# design.net
KiCad netlist of a schematic drawn in EasyEDA Pro
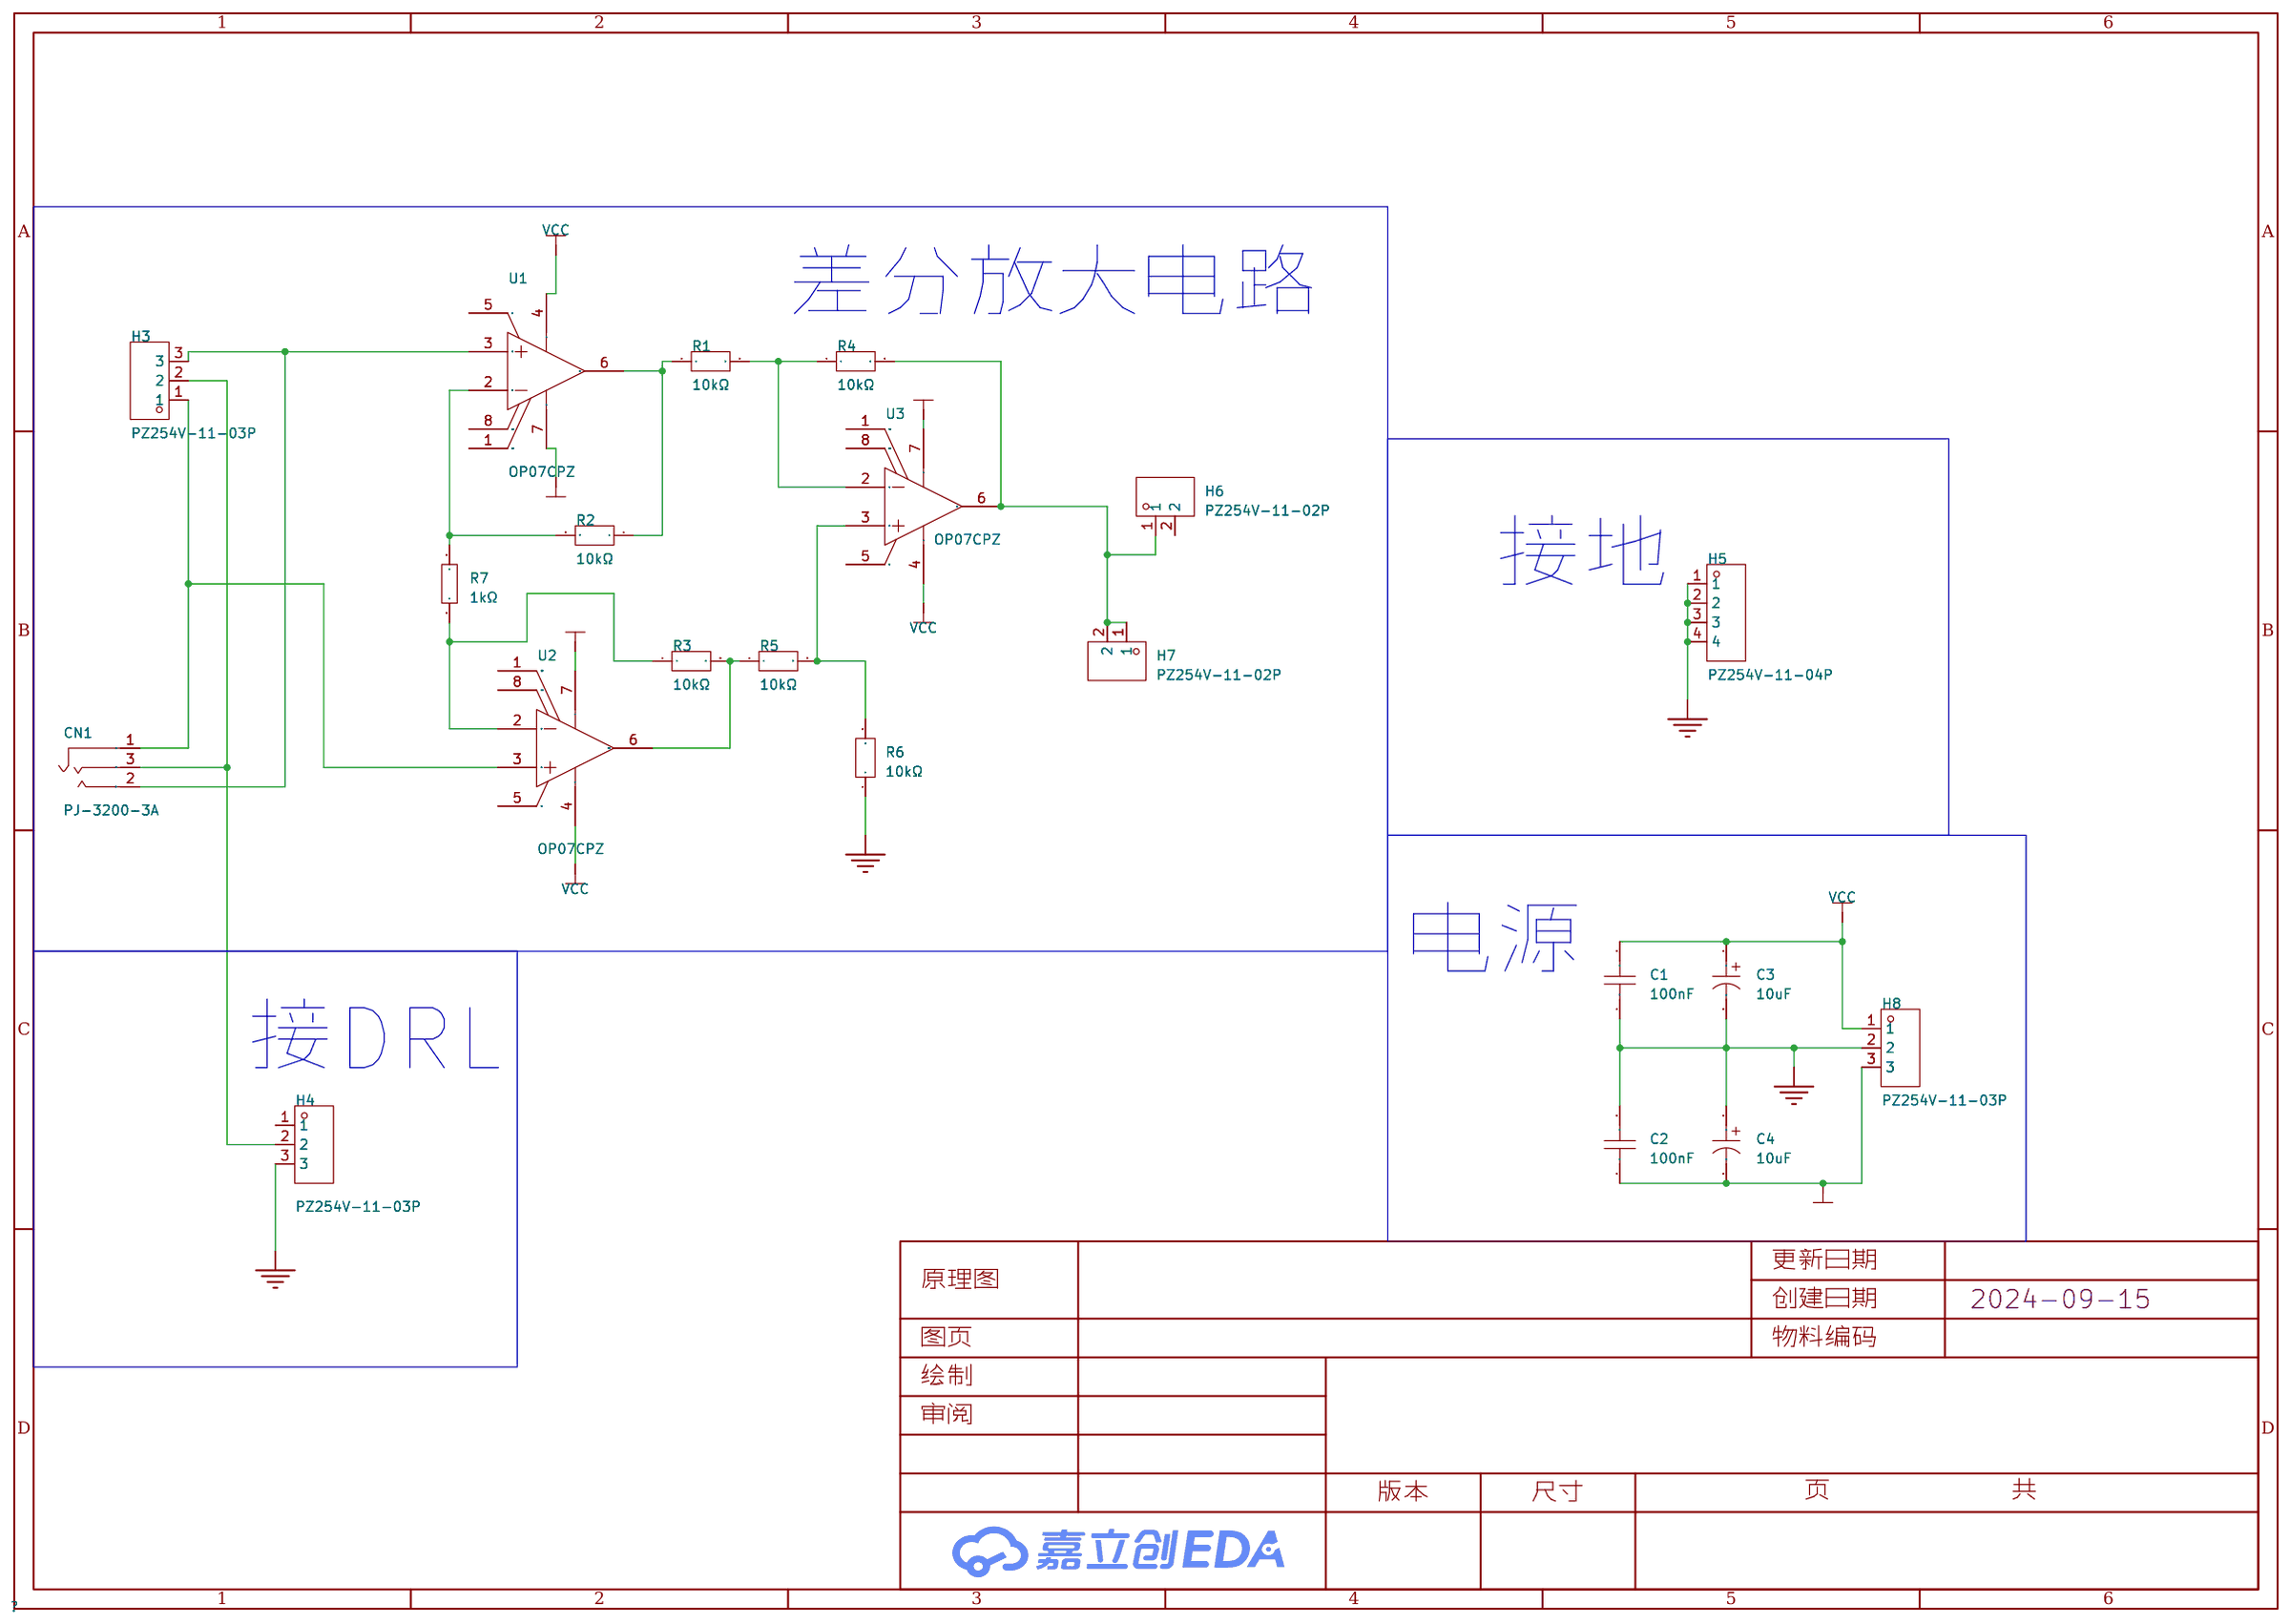
[diagram p0: schematic sheet]

(export (version "E")
  (design (tool "Eeschema 10.0.6"))
  (components
    (comp (ref "C1")
      (value "100nF")
      (footprint "easyedapro:CAP-TH_L13.0-W6.0-P10.0-D0.6")
      (description "容值:100nF;精度:±10%;电压(AC):275V;等级:X2;")
      (fields (field (name "Manufacturer Part") "1X2H410K275-11") (field (name "Manufacturer") "BM(丰明电容)"))
      (libsource (lib "easyedapro") (part "1X2H410K275-11"))
    )
    (comp (ref "C2")
      (value "100nF")
      (footprint "easyedapro:CAP-TH_L13.0-W6.0-P10.0-D0.6")
      (description "容值:100nF;精度:±10%;电压(AC):275V;等级:X2;")
      (fields (field (name "Manufacturer Part") "1X2H410K275-11") (field (name "Manufacturer") "BM(丰明电容)"))
      (libsource (lib "easyedapro") (part "1X2H410K275-11"))
    )
    (comp (ref "C3")
      (value "10uF")
      (footprint "easyedapro:CAP-TH_BD10.0-P5.00-D0.6-FD")
      (description "容值:10uF;精度:±20%;额定电压:250V;纹波电流:175mA@120Hz;等效串联电阻:-;")
      (fields
        (field (name "Manufacturer Part") "UCS2E100MPD1TD")
        (field (name "Manufacturer") "Nichicon(尼吉康)")
      )
      (libsource (lib "easyedapro") (part "UCS2E100MPD1TD"))
    )
    (comp (ref "C4")
      (value "10uF")
      (footprint "easyedapro:CAP-TH_BD10.0-P5.00-D0.6-FD")
      (description "容值:10uF;精度:±20%;额定电压:250V;纹波电流:175mA@120Hz;等效串联电阻:-;")
      (fields
        (field (name "Manufacturer Part") "UCS2E100MPD1TD")
        (field (name "Manufacturer") "Nichicon(尼吉康)")
      )
      (libsource (lib "easyedapro") (part "UCS2E100MPD1TD"))
    )
    (comp (ref "CN1")
      (value "PJ-3200-3A")
      (footprint "easyedapro:AUDIO-TH_PJ-3200-3A")
      (description "连接器类型:3.5mm耳机座;额定电流:500mA;额定电压:30V;工作温度范围:-20°C~+70°C;")
      (fields (field (name "Manufacturer") "韩国韩荣"))
      (libsource (lib "easyedapro") (part "PJ-3200-3A"))
    )
    (comp (ref "H3")
      (value "PZ254V-11-03P")
      (footprint "easyedapro:HDR-TH_3P-P2.54-V-M")
      (fields (field (name "Manufacturer") "XFCN(兴飞)"))
      (libsource (lib "easyedapro") (part "PZ254V-11-03P_C2937625"))
    )
    (comp (ref "H4")
      (value "PZ254V-11-03P")
      (footprint "easyedapro:HDR-TH_3P-P2.54-V-M")
      (fields (field (name "Manufacturer") "XFCN(兴飞)"))
      (libsource (lib "easyedapro") (part "PZ254V-11-03P_C2937625"))
    )
    (comp (ref "H5")
      (value "PZ254V-11-04P")
      (footprint "easyedapro:HDR-TH_4P-P2.54-V-M")
      (fields (field (name "Manufacturer") "XFCN(兴飞)"))
      (libsource (lib "easyedapro") (part "PZ254V-11-04P_C2691448"))
    )
    (comp (ref "H6")
      (value "PZ254V-11-02P")
      (footprint "easyedapro:HDR-TH_2P-P2.54-V-M")
      (fields (field (name "Manufacturer") "XFCN(兴飞)"))
      (libsource (lib "easyedapro") (part "PZ254V-11-02P"))
    )
    (comp (ref "H7")
      (value "PZ254V-11-02P")
      (footprint "easyedapro:HDR-TH_2P-P2.54-V-M")
      (fields (field (name "Manufacturer") "XFCN(兴飞)"))
      (libsource (lib "easyedapro") (part "PZ254V-11-02P"))
    )
    (comp (ref "H8")
      (value "PZ254V-11-03P")
      (footprint "easyedapro:HDR-TH_3P-P2.54-V-M")
      (fields (field (name "Manufacturer") "XFCN(兴飞)"))
      (libsource (lib "easyedapro") (part "PZ254V-11-03P_C2937625"))
    )
    (comp (ref "R1")
      (value "10kΩ")
      (footprint "easyedapro:RES-TH_BD2.4-L6.3-P10.30-D0.6")
      (description "电阻类型:金属膜电阻;阻值:10kΩ;精度:±1%;功率:250mW;温度系数:±50ppm/°C;")
      (fields
        (field (name "Manufacturer Part") "RN1/4W10KFT/BA1")
        (field (name "Manufacturer") "Tyohm(幸亚电阻)")
      )
      (libsource (lib "easyedapro") (part "RN 1/4W 10K F T/B A1"))
    )
    (comp (ref "R2")
      (value "10kΩ")
      (footprint "easyedapro:RES-TH_BD2.4-L6.3-P10.30-D0.6")
      (description "电阻类型:金属膜电阻;阻值:10kΩ;精度:±1%;功率:250mW;温度系数:±50ppm/°C;")
      (fields
        (field (name "Manufacturer Part") "RN1/4W10KFT/BA1")
        (field (name "Manufacturer") "Tyohm(幸亚电阻)")
      )
      (libsource (lib "easyedapro") (part "RN 1/4W 10K F T/B A1"))
    )
    (comp (ref "R3")
      (value "10kΩ")
      (footprint "easyedapro:RES-TH_BD2.4-L6.3-P10.30-D0.6")
      (description "电阻类型:金属膜电阻;阻值:10kΩ;精度:±1%;功率:250mW;温度系数:±50ppm/°C;")
      (fields
        (field (name "Manufacturer Part") "RN1/4W10KFT/BA1")
        (field (name "Manufacturer") "Tyohm(幸亚电阻)")
      )
      (libsource (lib "easyedapro") (part "RN 1/4W 10K F T/B A1"))
    )
    (comp (ref "R4")
      (value "10kΩ")
      (footprint "easyedapro:RES-TH_BD2.4-L6.3-P10.30-D0.6")
      (description "电阻类型:金属膜电阻;阻值:10kΩ;精度:±1%;功率:250mW;温度系数:±50ppm/°C;")
      (fields
        (field (name "Manufacturer Part") "RN1/4W10KFT/BA1")
        (field (name "Manufacturer") "Tyohm(幸亚电阻)")
      )
      (libsource (lib "easyedapro") (part "RN 1/4W 10K F T/B A1"))
    )
    (comp (ref "R5")
      (value "10kΩ")
      (footprint "easyedapro:RES-TH_BD2.4-L6.3-P10.30-D0.6")
      (description "电阻类型:金属膜电阻;阻值:10kΩ;精度:±1%;功率:250mW;温度系数:±50ppm/°C;")
      (fields
        (field (name "Manufacturer Part") "RN1/4W10KFT/BA1")
        (field (name "Manufacturer") "Tyohm(幸亚电阻)")
      )
      (libsource (lib "easyedapro") (part "RN 1/4W 10K F T/B A1"))
    )
    (comp (ref "R6")
      (value "10kΩ")
      (footprint "easyedapro:RES-TH_BD2.4-L6.3-P10.30-D0.6")
      (description "电阻类型:金属膜电阻;阻值:10kΩ;精度:±1%;功率:250mW;温度系数:±50ppm/°C;")
      (fields
        (field (name "Manufacturer Part") "RN1/4W10KFT/BA1")
        (field (name "Manufacturer") "Tyohm(幸亚电阻)")
      )
      (libsource (lib "easyedapro") (part "RN 1/4W 10K F T/B A1"))
    )
    (comp (ref "R7")
      (value "1kΩ")
      (footprint "easyedapro:RES-TH_BD2.5-L6.5-P10.50-D0.6")
      (description "电阻类型:金属膜电阻;阻值:1kΩ;精度:±1%;功率:250mW;温度系数:±50ppm/°C;")
      (fields
        (field (name "Manufacturer Part") "MFR0W4F1001A50")
        (field (name "Manufacturer") "UNI-ROYAL(厚声)")
      )
      (libsource (lib "easyedapro") (part "MFR0W4F1001A50"))
    )
    (comp (ref "U1")
      (value "OP07CPZ")
      (footprint "easyedapro:PDIP-8_L9.3-W6.4-P2.54-LS7.6-BL")
      (description "超低失调电压运算放大器")
      (fields (field (name "Manufacturer") "ADI(亚德诺)"))
      (libsource (lib "easyedapro") (part "OP07CPZ"))
    )
    (comp (ref "U2")
      (value "OP07CPZ")
      (footprint "easyedapro:PDIP-8_L9.3-W6.4-P2.54-LS7.6-BL")
      (description "超低失调电压运算放大器")
      (fields (field (name "Manufacturer") "ADI(亚德诺)"))
      (libsource (lib "easyedapro") (part "OP07CPZ"))
    )
    (comp (ref "U3")
      (value "OP07CPZ")
      (footprint "easyedapro:PDIP-8_L9.3-W6.4-P2.54-LS7.6-BL")
      (description "超低失调电压运算放大器")
      (fields (field (name "Manufacturer") "ADI(亚德诺)"))
      (libsource (lib "easyedapro") (part "OP07CPZ"))
    )
  )
  (nets
    (net (code "1") (name "GND") (class "Default")
      (node (ref "C1") (pin "1") (pinfunction "1_1") (pintype "unspecified"))
      (node (ref "C2") (pin "2") (pinfunction "2_2") (pintype "unspecified"))
      (node (ref "C3") (pin "2") (pinfunction "2_2") (pintype "input"))
      (node (ref "C4") (pin "1") (pinfunction "1_1") (pintype "input"))
      (node (ref "H4") (pin "3") (pinfunction "3_3") (pintype "unspecified"))
      (node (ref "H5") (pin "1") (pinfunction "1_1") (pintype "unspecified"))
      (node (ref "H5") (pin "2") (pinfunction "2_2") (pintype "unspecified"))
      (node (ref "H5") (pin "3") (pinfunction "3_3") (pintype "unspecified"))
      (node (ref "H5") (pin "4") (pinfunction "4_4") (pintype "unspecified"))
      (node (ref "H8") (pin "2") (pinfunction "2_2") (pintype "unspecified"))
      (node (ref "R6") (pin "1") (pinfunction "1_1") (pintype "unspecified"))
    )
    (net (code "2") (name "Net-(CN1-Pad3)") (class "Default")
      (node (ref "CN1") (pin "3") (pinfunction "3_3") (pintype "unspecified"))
      (node (ref "H3") (pin "2") (pinfunction "2_2") (pintype "unspecified"))
      (node (ref "H4") (pin "2") (pinfunction "2_2") (pintype "unspecified"))
    )
    (net (code "3") (name "Net-(U1-IN+)") (class "Default")
      (node (ref "CN1") (pin "2") (pinfunction "2_2") (pintype "unspecified"))
      (node (ref "H3") (pin "3") (pinfunction "3_3") (pintype "unspecified"))
      (node (ref "U1") (pin "3") (pinfunction "IN+_3") (pintype "unspecified"))
    )
    (net (code "4") (name "Net-(U1-IN-)") (class "Default")
      (node (ref "R2") (pin "2") (pinfunction "2_2") (pintype "unspecified"))
      (node (ref "R7") (pin "2") (pinfunction "2_2") (pintype "input"))
      (node (ref "U1") (pin "2") (pinfunction "IN-_2") (pintype "unspecified"))
    )
    (net (code "5") (name "Net-(U1-OUT)") (class "Default")
      (node (ref "R1") (pin "1") (pinfunction "1_1") (pintype "unspecified"))
      (node (ref "R2") (pin "1") (pinfunction "1_1") (pintype "unspecified"))
      (node (ref "U1") (pin "6") (pinfunction "OUT_6") (pintype "output"))
    )
    (net (code "6") (name "Net-(U2-IN+)") (class "Default")
      (node (ref "CN1") (pin "1") (pinfunction "1_1") (pintype "unspecified"))
      (node (ref "H3") (pin "1") (pinfunction "1_1") (pintype "unspecified"))
      (node (ref "U2") (pin "3") (pinfunction "IN+_3") (pintype "unspecified"))
    )
    (net (code "7") (name "Net-(U2-IN-)") (class "Default")
      (node (ref "R3") (pin "1") (pinfunction "1_1") (pintype "unspecified"))
      (node (ref "R7") (pin "1") (pinfunction "1_1") (pintype "input"))
      (node (ref "U2") (pin "2") (pinfunction "IN-_2") (pintype "unspecified"))
    )
    (net (code "8") (name "Net-(U2-OUT)") (class "Default")
      (node (ref "R3") (pin "2") (pinfunction "2_2") (pintype "unspecified"))
      (node (ref "R5") (pin "1") (pinfunction "1_1") (pintype "unspecified"))
      (node (ref "U2") (pin "6") (pinfunction "OUT_6") (pintype "output"))
    )
    (net (code "9") (name "Net-(U3-IN+)") (class "Default")
      (node (ref "R5") (pin "2") (pinfunction "2_2") (pintype "unspecified"))
      (node (ref "R6") (pin "2") (pinfunction "2_2") (pintype "unspecified"))
      (node (ref "U3") (pin "3") (pinfunction "IN+_3") (pintype "unspecified"))
    )
    (net (code "10") (name "Net-(U3-IN-)") (class "Default")
      (node (ref "R1") (pin "2") (pinfunction "2_2") (pintype "unspecified"))
      (node (ref "R4") (pin "1") (pinfunction "1_1") (pintype "unspecified"))
      (node (ref "U3") (pin "2") (pinfunction "IN-_2") (pintype "unspecified"))
    )
    (net (code "11") (name "Net-(U3-OUT)") (class "Default")
      (node (ref "H6") (pin "1") (pinfunction "1_1") (pintype "unspecified"))
      (node (ref "H7") (pin "1") (pinfunction "1_1") (pintype "unspecified"))
      (node (ref "H7") (pin "2") (pinfunction "2_2") (pintype "unspecified"))
      (node (ref "R4") (pin "2") (pinfunction "2_2") (pintype "unspecified"))
      (node (ref "U3") (pin "6") (pinfunction "OUT_6") (pintype "output"))
    )
    (net (code "12") (name "VCC") (class "Default")
      (node (ref "C1") (pin "2") (pinfunction "2_2") (pintype "unspecified"))
      (node (ref "C3") (pin "1") (pinfunction "1_1") (pintype "input"))
      (node (ref "H8") (pin "1") (pinfunction "1_1") (pintype "unspecified"))
      (node (ref "U1") (pin "4") (pinfunction "V-_4") (pintype "unspecified"))
      (node (ref "U2") (pin "4") (pinfunction "V-_4") (pintype "unspecified"))
      (node (ref "U3") (pin "4") (pinfunction "V-_4") (pintype "unspecified"))
    )
    (net (code "13") (name "VEE") (class "Default")
      (node (ref "C2") (pin "1") (pinfunction "1_1") (pintype "unspecified"))
      (node (ref "C4") (pin "2") (pinfunction "2_2") (pintype "input"))
      (node (ref "H8") (pin "3") (pinfunction "3_3") (pintype "unspecified"))
      (node (ref "U1") (pin "7") (pinfunction "V+_7") (pintype "unspecified"))
      (node (ref "U2") (pin "7") (pinfunction "V+_7") (pintype "unspecified"))
      (node (ref "U3") (pin "7") (pinfunction "V+_7") (pintype "unspecified"))
    )
    (net (code "14") (name "unconnected-(H4-Pad1)") (class "Default")
      (node (ref "H4") (pin "1") (pinfunction "1_1") (pintype "unspecified"))
    )
    (net (code "15") (name "unconnected-(H6-Pad2)") (class "Default")
      (node (ref "H6") (pin "2") (pinfunction "2_2") (pintype "unspecified"))
    )
    (net (code "16") (name "unconnected-(U1-NC-Pad5)") (class "Default")
      (node (ref "U1") (pin "5") (pinfunction "NC_5") (pintype "unspecified"))
    )
    (net (code "17") (name "unconnected-(U1-VOS_TRIM-Pad1)") (class "Default")
      (node (ref "U1") (pin "1") (pinfunction "VOS_TRIM_1") (pintype "unspecified"))
    )
    (net (code "18") (name "unconnected-(U1-VOS_TRIM-Pad8)") (class "Default")
      (node (ref "U1") (pin "8") (pinfunction "VOS_TRIM_8") (pintype "unspecified"))
    )
    (net (code "19") (name "unconnected-(U2-NC-Pad5)") (class "Default")
      (node (ref "U2") (pin "5") (pinfunction "NC_5") (pintype "unspecified"))
    )
    (net (code "20") (name "unconnected-(U2-VOS_TRIM-Pad1)") (class "Default")
      (node (ref "U2") (pin "1") (pinfunction "VOS_TRIM_1") (pintype "unspecified"))
    )
    (net (code "21") (name "unconnected-(U2-VOS_TRIM-Pad8)") (class "Default")
      (node (ref "U2") (pin "8") (pinfunction "VOS_TRIM_8") (pintype "unspecified"))
    )
    (net (code "22") (name "unconnected-(U3-NC-Pad5)") (class "Default")
      (node (ref "U3") (pin "5") (pinfunction "NC_5") (pintype "unspecified"))
    )
    (net (code "23") (name "unconnected-(U3-VOS_TRIM-Pad1)") (class "Default")
      (node (ref "U3") (pin "1") (pinfunction "VOS_TRIM_1") (pintype "unspecified"))
    )
    (net (code "24") (name "unconnected-(U3-VOS_TRIM-Pad8)") (class "Default")
      (node (ref "U3") (pin "8") (pinfunction "VOS_TRIM_8") (pintype "unspecified"))
    )
  )
)
